# design.net
KiCad netlist of a schematic drawn in Altium Designer
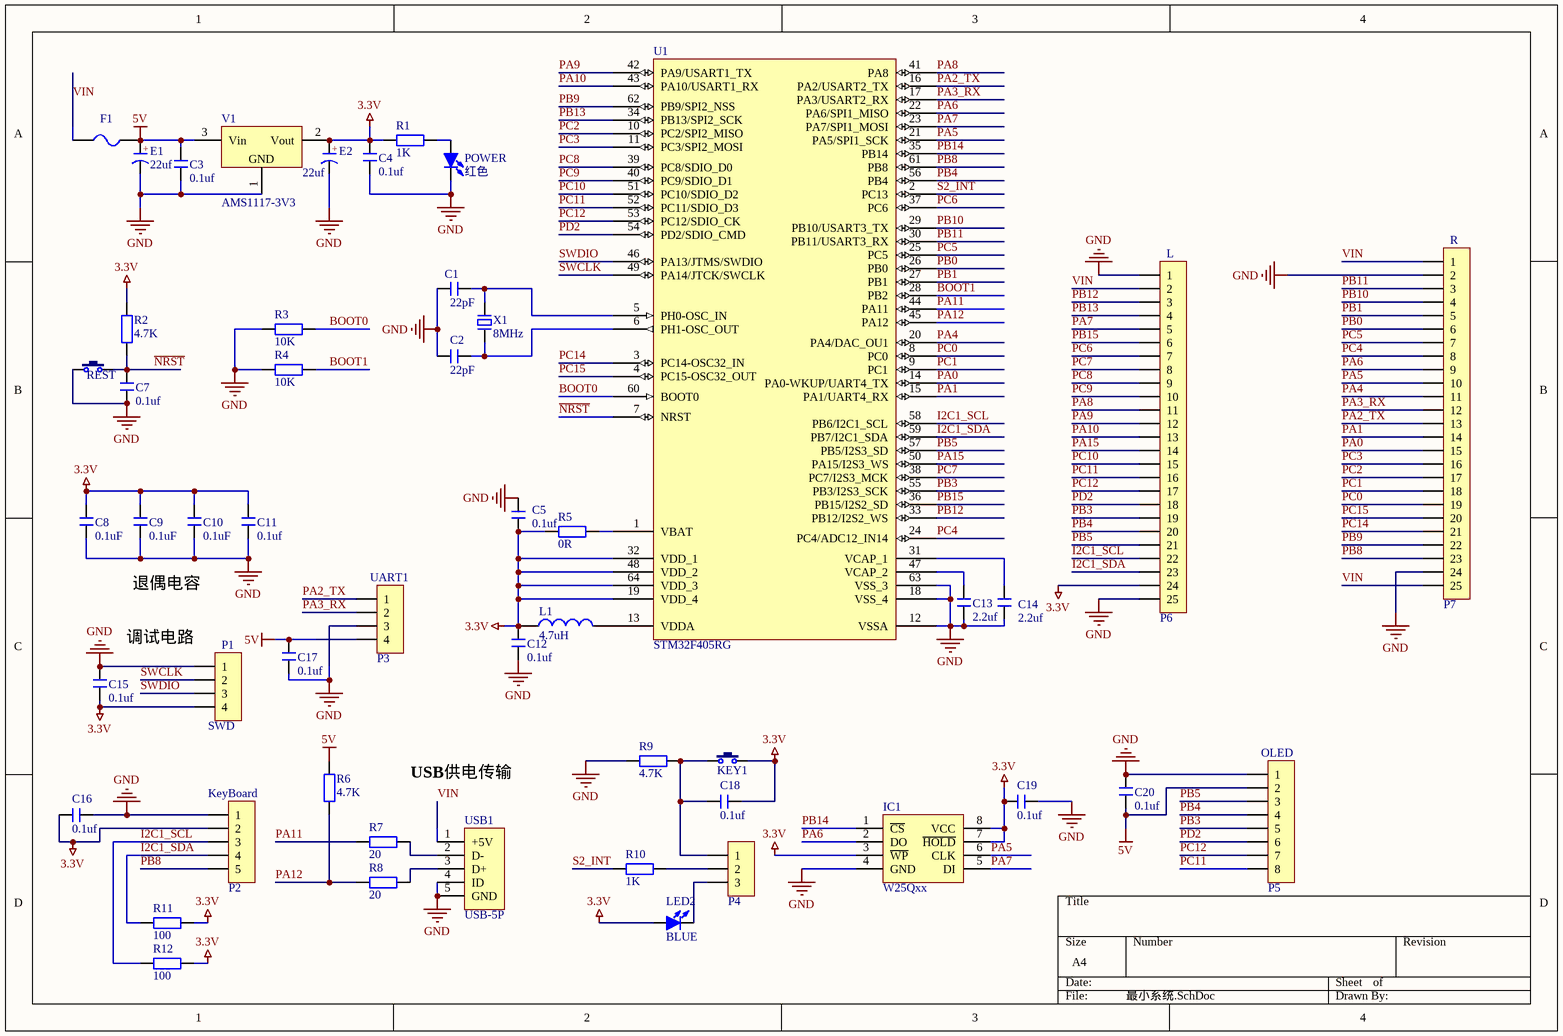
[diagram p0: 最小系统.SchDoc]

(export (version "E")
  (design (tool "Eeschema 10.0.6"))
  (components
    (comp (ref "C1")
      (value "22pF")
      (footprint "C 0603_M")
      (description "无极性贴片电容")
      (fields (field (name "版权归属") "源创客"))
      (libsource (lib "3.1   - 电阻-电容-电感") (part "C"))
    )
    (comp (ref "C2")
      (value "22pF")
      (footprint "C 0603_M")
      (description "无极性贴片电容")
      (fields (field (name "版权归属") "源创客"))
      (libsource (lib "3.1   - 电阻-电容-电感") (part "C"))
    )
    (comp (ref "C3")
      (value "0.1uf")
      (footprint "C 0603_M")
      (description "无极性贴片电容")
      (fields (field (name "版权归属") "源创客"))
      (libsource (lib "3.1   - 电阻-电容-电感") (part "C"))
    )
    (comp (ref "C4")
      (value "0.1uf")
      (footprint "C 0603_M")
      (description "无极性贴片电容")
      (fields (field (name "版权归属") "源创客"))
      (libsource (lib "3.1   - 电阻-电容-电感") (part "C"))
    )
    (comp (ref "C5")
      (value "0.1uf")
      (footprint "C 0603_M")
      (description "无极性贴片电容")
      (fields (field (name "版权归属") "源创客"))
      (libsource (lib "3.1   - 电阻-电容-电感") (part "C"))
    )
    (comp (ref "C7")
      (value "0.1uf")
      (footprint "C 0603_M")
      (description "无极性贴片电容")
      (fields (field (name "版权归属") "源创客"))
      (libsource (lib "3.1   - 电阻-电容-电感") (part "C"))
    )
    (comp (ref "C8")
      (value "0.1uF")
      (footprint "C 0603_M")
      (description "无极性贴片电容")
      (fields (field (name "版权归属") "源创客"))
      (libsource (lib "3.1   - 电阻-电容-电感") (part "C"))
    )
    (comp (ref "C9")
      (value "0.1uF")
      (footprint "C 0603_M")
      (description "无极性贴片电容")
      (fields (field (name "版权归属") "源创客"))
      (libsource (lib "3.1   - 电阻-电容-电感") (part "C"))
    )
    (comp (ref "C10")
      (value "0.1uF")
      (footprint "C 0603_M")
      (description "无极性贴片电容")
      (fields (field (name "版权归属") "源创客"))
      (libsource (lib "3.1   - 电阻-电容-电感") (part "C"))
    )
    (comp (ref "C11")
      (value "0.1uf")
      (footprint "C 0603_M")
      (description "无极性贴片电容")
      (fields (field (name "版权归属") "源创客"))
      (libsource (lib "3.1   - 电阻-电容-电感") (part "C"))
    )
    (comp (ref "C12")
      (value "0.1uf")
      (footprint "C 0603_M")
      (description "无极性贴片电容")
      (fields (field (name "版权归属") "源创客"))
      (libsource (lib "3.1   - 电阻-电容-电感") (part "C"))
    )
    (comp (ref "C13")
      (value "2.2uf")
      (footprint "C 0603_M")
      (description "无极性贴片电容")
      (fields (field (name "版权归属") "源创客"))
      (libsource (lib "3.1   - 电阻-电容-电感") (part "C"))
    )
    (comp (ref "C14")
      (value "2.2uf")
      (footprint "C 0603_M")
      (description "无极性贴片电容")
      (fields (field (name "版权归属") "源创客"))
      (libsource (lib "3.1   - 电阻-电容-电感") (part "C"))
    )
    (comp (ref "C15")
      (value "0.1uf")
      (footprint "C 0603_M")
      (description "无极性贴片电容")
      (fields (field (name "版权归属") "源创客"))
      (libsource (lib "3.1   - 电阻-电容-电感") (part "C"))
    )
    (comp (ref "C16")
      (value "0.1uf")
      (footprint "C 0603_M")
      (description "无极性贴片电容")
      (fields (field (name "版权归属") "源创客"))
      (libsource (lib "3.1   - 电阻-电容-电感") (part "C"))
    )
    (comp (ref "C17")
      (value "0.1uf")
      (footprint "C 0603_M")
      (description "无极性贴片电容")
      (fields (field (name "版权归属") "源创客"))
      (libsource (lib "3.1   - 电阻-电容-电感") (part "C"))
    )
    (comp (ref "C18")
      (value "0.1uf")
      (footprint "C 0603_M")
      (description "无极性贴片电容")
      (fields (field (name "版权归属") "源创客"))
      (libsource (lib "3.1   - 电阻-电容-电感") (part "C"))
    )
    (comp (ref "C19")
      (value "0.1uf")
      (footprint "C 0603_M")
      (description "无极性贴片电容")
      (fields (field (name "版权归属") "源创客"))
      (libsource (lib "3.1   - 电阻-电容-电感") (part "C"))
    )
    (comp (ref "C20")
      (value "0.1uf")
      (footprint "C 0603_M")
      (description "无极性贴片电容")
      (fields (field (name "版权归属") "源创客"))
      (libsource (lib "3.1   - 电阻-电容-电感") (part "C"))
    )
    (comp (ref "E1")
      (value "22uf")
      (footprint "CD B(3528)")
      (description "贴片钽电容")
      (fields (field (name "版权归属") "源创客"))
      (libsource (lib "3.1   - 电阻-电容-电感") (part "C-CD"))
    )
    (comp (ref "E2")
      (value "22uf")
      (footprint "CD B(3528)")
      (description "贴片钽电容")
      (fields (field (name "版权归属") "源创客"))
      (libsource (lib "3.1   - 电阻-电容-电感") (part "C-CD"))
    )
    (comp (ref "F1")
      (value "~")
      (footprint "FU 0603")
      (description "贴片保险丝")
      (fields (field (name "版权归属") "源创客"))
      (libsource (lib "10.1 - 保险丝-晶振") (part "FU"))
    )
    (comp (ref "IC1")
      (value "W25Qxx")
      (footprint "SOP8W_L")
      (description "外置Flash")
      (fields (field (name "版权归属") "源创客"))
      (libsource (lib "1.1   - IC芯片") (part "W25Qxx"))
    )
    (comp (ref "KEY1")
      (value "3x6x5")
      (footprint "TSW SMD-3*6*5")
      (description "3x6轻触开关")
      (fields (field (name "版权归属") "源创客"))
      (libsource (lib "5.1   - 按键-开关") (part "TSW 3x6"))
    )
    (comp (ref "L1")
      (value "4.7uH")
      (footprint "L 0603")
      (description "小功率贴片电感")
      (fields (field (name "版权归属") "源创客"))
      (libsource (lib "3.1   - 电阻-电容-电感") (part "L"))
    )
    (comp (ref "LED2")
      (value "BLUE")
      (footprint "LED 0603B")
      (description "贴片LED")
      (fields (field (name "版权归属") "源创客"))
      (libsource (lib "9.1   - LED") (part "LED-SMD"))
    )
    (comp (ref "P1")
      (value "HDR-1X4")
      (footprint "HDR2.54-LI-4P")
      (description "4P接插件")
      (fields (field (name "版权归属") "源创客"))
      (libsource (lib "4.5   - 接插件-脚距2.54") (part "Header 4"))
    )
    (comp (ref "P2")
      (value "HDR-1X5")
      (footprint "HDR2.54-LI-5P")
      (description "5P接插件")
      (fields (field (name "版权归属") "源创客"))
      (libsource (lib "4.5   - 接插件-脚距2.54") (part "Header 5"))
    )
    (comp (ref "P3")
      (value "HDR-1X4")
      (footprint "HDR2.54-LI-4P")
      (description "4P接插件")
      (fields (field (name "版权归属") "源创客"))
      (libsource (lib "4.5   - 接插件-脚距2.54") (part "Header 4"))
    )
    (comp (ref "P4")
      (value "HDR-1X3")
      (footprint "HDR2.54-LI-3P")
      (description "3P接插件")
      (fields (field (name "版权归属") "源创客"))
      (libsource (lib "4.5   - 接插件-脚距2.54") (part "Header 3"))
    )
    (comp (ref "P5")
      (value "HDR-1X8")
      (footprint "HDR2.54-LI-8P")
      (description "8P接插件")
      (fields (field (name "版权归属") "源创客"))
      (libsource (lib "4.5   - 接插件-脚距2.54") (part "Header 8"))
    )
    (comp (ref "P6")
      (value "FPC1.0-25P")
      (footprint "HDR2.54-L1-25P")
      (description "FPC连接器")
      (fields (field (name "版权归属") "源创客"))
      (libsource (lib "4.14 - FPC连接器") (part "FPC-25P"))
    )
    (comp (ref "P7")
      (value "FPC1.0-25P")
      (footprint "HDR2.54-L1-25P")
      (description "FPC连接器")
      (fields (field (name "版权归属") "源创客"))
      (libsource (lib "4.14 - FPC连接器") (part "FPC-25P"))
    )
    (comp (ref "POWER")
      (value "红色")
      (footprint "LED 0603W")
      (description "贴片LED")
      (fields (field (name "版权归属") "源创客"))
      (libsource (lib "9.1   - LED") (part "LED-SMD"))
    )
    (comp (ref "R1")
      (value "1K")
      (footprint "R 0603_M")
      (description "贴片电阻")
      (fields (field (name "版权归属") "源创客"))
      (libsource (lib "3.1   - 电阻-电容-电感") (part "R"))
    )
    (comp (ref "R2")
      (value "4.7K")
      (footprint "R 0603_M")
      (description "贴片电阻")
      (fields (field (name "版权归属") "源创客"))
      (libsource (lib "3.1   - 电阻-电容-电感") (part "R"))
    )
    (comp (ref "R3")
      (value "10K")
      (footprint "R 0603_M")
      (description "贴片电阻")
      (fields (field (name "版权归属") "源创客"))
      (libsource (lib "3.1   - 电阻-电容-电感") (part "R"))
    )
    (comp (ref "R4")
      (value "10K")
      (footprint "R 0603_M")
      (description "贴片电阻")
      (fields (field (name "版权归属") "源创客"))
      (libsource (lib "3.1   - 电阻-电容-电感") (part "R"))
    )
    (comp (ref "R5")
      (value "0R")
      (footprint "R 0603_M")
      (description "贴片电阻")
      (fields (field (name "版权归属") "源创客"))
      (libsource (lib "3.1   - 电阻-电容-电感") (part "R"))
    )
    (comp (ref "R6")
      (value "4.7K")
      (footprint "R 0603_M")
      (description "贴片电阻")
      (fields (field (name "版权归属") "源创客"))
      (libsource (lib "3.1   - 电阻-电容-电感") (part "R"))
    )
    (comp (ref "R7")
      (value "20")
      (footprint "R 0603_M")
      (description "贴片电阻")
      (fields (field (name "版权归属") "源创客"))
      (libsource (lib "3.1   - 电阻-电容-电感") (part "R"))
    )
    (comp (ref "R8")
      (value "20")
      (footprint "R 0603_M")
      (description "贴片电阻")
      (fields (field (name "版权归属") "源创客"))
      (libsource (lib "3.1   - 电阻-电容-电感") (part "R"))
    )
    (comp (ref "R9")
      (value "4.7K")
      (footprint "R 0603_M")
      (description "贴片电阻")
      (fields (field (name "版权归属") "源创客"))
      (libsource (lib "3.1   - 电阻-电容-电感") (part "R"))
    )
    (comp (ref "R10")
      (value "1K")
      (footprint "R 0603_M")
      (description "贴片电阻")
      (fields (field (name "版权归属") "源创客"))
      (libsource (lib "3.1   - 电阻-电容-电感") (part "R"))
    )
    (comp (ref "R11")
      (value "100")
      (footprint "R 0603_M")
      (description "贴片电阻")
      (fields (field (name "版权归属") "源创客"))
      (libsource (lib "3.1   - 电阻-电容-电感") (part "R"))
    )
    (comp (ref "R12")
      (value "100")
      (footprint "R 0603_M")
      (description "贴片电阻")
      (fields (field (name "版权归属") "源创客"))
      (libsource (lib "3.1   - 电阻-电容-电感") (part "R"))
    )
    (comp (ref "REST")
      (value "3x6x5")
      (footprint "TSW SMD-3*6*5")
      (description "3x6轻触开关")
      (fields (field (name "版权归属") "源创客"))
      (libsource (lib "5.1   - 按键-开关") (part "TSW 3x6"))
    )
    (comp (ref "U1")
      (value "STM32F405RG")
      (footprint "LQFP64 10X10_N")
      (description "32位STM单片机")
      (fields (field (name "版权归属") "源创客"))
      (libsource (lib "2.1   - STM32系列单片机") (part "STM32F205RG"))
    )
    (comp (ref "USB1")
      (value "USB-5P")
      (footprint "USB-MICRO_E")
      (description "微型USB母座")
      (fields (field (name "版权归属") "源创客"))
      (libsource (lib "4.1   - 接口类") (part "USB-5P"))
    )
    (comp (ref "V1")
      (value "AMS1117-3V3")
      (footprint "SOT223_L")
      (description "三端稳压芯片")
      (fields (field (name "版权归属") "源创客"))
      (libsource (lib "1.3   - 电源类芯片") (part "AMS1117"))
    )
    (comp (ref "X1")
      (value "8MHz")
      (footprint "OSC 5032-2P")
      (description "2脚无源脚晶振")
      (fields (field (name "版权归属") "源创客"))
      (libsource (lib "10.1 - 保险丝-晶振") (part "XTAL-2P"))
    )
  )
  (nets
    (net (code "1") (name "/BOOT0") (class "Default")
      (node (ref "R3") (pin "2") (pinfunction "2_2") (pintype "passive"))
      (node (ref "U1") (pin "60") (pinfunction "BOOT0_60") (pintype "input"))
    )
    (net (code "2") (name "/BOOT1") (class "Default")
      (node (ref "R4") (pin "2") (pinfunction "2_2") (pintype "passive"))
      (node (ref "U1") (pin "28") (pinfunction "PB2_28") (pintype "bidirectional"))
    )
    (net (code "3") (name "/I2C1_SCL") (class "Default")
      (node (ref "P2") (pin "3") (pinfunction "3_3") (pintype "passive"))
      (node (ref "P6") (pin "22") (pinfunction "22_22") (pintype "passive"))
      (node (ref "R12") (pin "1") (pinfunction "1_1") (pintype "passive"))
      (node (ref "U1") (pin "58") (pinfunction "PB6/I2C1_SCL_58") (pintype "bidirectional"))
    )
    (net (code "4") (name "/I2C1_SDA") (class "Default")
      (node (ref "P2") (pin "4") (pinfunction "4_4") (pintype "passive"))
      (node (ref "P6") (pin "23") (pinfunction "23_23") (pintype "passive"))
      (node (ref "R11") (pin "1") (pinfunction "1_1") (pintype "passive"))
      (node (ref "U1") (pin "59") (pinfunction "PB7/I2C1_SDA_59") (pintype "bidirectional"))
    )
    (net (code "5") (name "/PA0") (class "Default")
      (node (ref "P7") (pin "15") (pinfunction "15_15") (pintype "passive"))
      (node (ref "U1") (pin "14") (pinfunction "PA0-WKUP/UART4_TX_14") (pintype "bidirectional"))
    )
    (net (code "6") (name "/PA1") (class "Default")
      (node (ref "P7") (pin "14") (pinfunction "14_14") (pintype "passive"))
      (node (ref "U1") (pin "15") (pinfunction "PA1/UART4_RX_15") (pintype "bidirectional"))
    )
    (net (code "7") (name "/PA2_TX") (class "Default")
      (node (ref "P3") (pin "1") (pinfunction "1_1") (pintype "passive"))
      (node (ref "P7") (pin "13") (pinfunction "13_13") (pintype "passive"))
      (node (ref "U1") (pin "16") (pinfunction "PA2/USART2_TX_16") (pintype "bidirectional"))
    )
    (net (code "8") (name "/PA3_RX") (class "Default")
      (node (ref "P3") (pin "2") (pinfunction "2_2") (pintype "passive"))
      (node (ref "P7") (pin "12") (pinfunction "12_12") (pintype "passive"))
      (node (ref "U1") (pin "17") (pinfunction "PA3/USART2_RX_17") (pintype "bidirectional"))
    )
    (net (code "9") (name "/PA4") (class "Default")
      (node (ref "P7") (pin "11") (pinfunction "11_11") (pintype "passive"))
      (node (ref "U1") (pin "20") (pinfunction "PA4/DAC_OU1_20") (pintype "bidirectional"))
    )
    (net (code "10") (name "/PA5") (class "Default")
      (node (ref "IC1") (pin "6") (pinfunction "CLK_6") (pintype "passive"))
      (node (ref "P7") (pin "10") (pinfunction "10_10") (pintype "passive"))
      (node (ref "U1") (pin "21") (pinfunction "PA5/SPI1_SCK_21") (pintype "bidirectional"))
    )
    (net (code "11") (name "/PA6") (class "Default")
      (node (ref "IC1") (pin "2") (pinfunction "DO_2") (pintype "passive"))
      (node (ref "P7") (pin "9") (pinfunction "9_9") (pintype "passive"))
      (node (ref "U1") (pin "22") (pinfunction "PA6/SPI1_MISO_22") (pintype "bidirectional"))
    )
    (net (code "12") (name "/PA7") (class "Default")
      (node (ref "IC1") (pin "5") (pinfunction "DI_5") (pintype "passive"))
      (node (ref "P6") (pin "5") (pinfunction "5_5") (pintype "passive"))
      (node (ref "U1") (pin "23") (pinfunction "PA7/SPI1_MOSI_23") (pintype "bidirectional"))
    )
    (net (code "13") (name "/PA8") (class "Default")
      (node (ref "P6") (pin "11") (pinfunction "11_11") (pintype "passive"))
      (node (ref "U1") (pin "41") (pinfunction "PA8_41") (pintype "bidirectional"))
    )
    (net (code "14") (name "/PA9") (class "Default")
      (node (ref "P6") (pin "12") (pinfunction "12_12") (pintype "passive"))
      (node (ref "U1") (pin "42") (pinfunction "PA9/USART1_TX_42") (pintype "bidirectional"))
    )
    (net (code "15") (name "/PA10") (class "Default")
      (node (ref "P6") (pin "13") (pinfunction "13_13") (pintype "passive"))
      (node (ref "U1") (pin "43") (pinfunction "PA10/USART1_RX_43") (pintype "bidirectional"))
    )
    (net (code "16") (name "/PA11") (class "Default")
      (node (ref "R7") (pin "1") (pinfunction "1_1") (pintype "passive"))
      (node (ref "U1") (pin "44") (pinfunction "PA11_44") (pintype "bidirectional"))
    )
    (net (code "17") (name "/PA12") (class "Default")
      (node (ref "R6") (pin "1") (pinfunction "1_1") (pintype "passive"))
      (node (ref "R8") (pin "1") (pinfunction "1_1") (pintype "passive"))
      (node (ref "U1") (pin "45") (pinfunction "PA12_45") (pintype "bidirectional"))
    )
    (net (code "18") (name "/PA15") (class "Default")
      (node (ref "P6") (pin "14") (pinfunction "14_14") (pintype "passive"))
      (node (ref "U1") (pin "50") (pinfunction "PA15/I2S3_WS_50") (pintype "bidirectional"))
    )
    (net (code "19") (name "/PB0") (class "Default")
      (node (ref "P7") (pin "6") (pinfunction "6_6") (pintype "passive"))
      (node (ref "U1") (pin "26") (pinfunction "PB0_26") (pintype "bidirectional"))
    )
    (net (code "20") (name "/PB1") (class "Default")
      (node (ref "P7") (pin "5") (pinfunction "5_5") (pintype "passive"))
      (node (ref "U1") (pin "27") (pinfunction "PB1_27") (pintype "bidirectional"))
    )
    (net (code "21") (name "/PB3") (class "Default")
      (node (ref "P5") (pin "5") (pinfunction "5_5") (pintype "passive"))
      (node (ref "P6") (pin "19") (pinfunction "19_19") (pintype "passive"))
      (node (ref "U1") (pin "55") (pinfunction "PB3/I2S3_SCK_55") (pintype "bidirectional"))
    )
    (net (code "22") (name "/PB4") (class "Default")
      (node (ref "P5") (pin "4") (pinfunction "4_4") (pintype "passive"))
      (node (ref "P6") (pin "20") (pinfunction "20_20") (pintype "passive"))
      (node (ref "U1") (pin "56") (pinfunction "PB4_56") (pintype "bidirectional"))
    )
    (net (code "23") (name "/PB5") (class "Default")
      (node (ref "P5") (pin "3") (pinfunction "3_3") (pintype "passive"))
      (node (ref "P6") (pin "21") (pinfunction "21_21") (pintype "passive"))
      (node (ref "U1") (pin "57") (pinfunction "PB5/I2S3_SD_57") (pintype "bidirectional"))
    )
    (net (code "24") (name "/PB8") (class "Default")
      (node (ref "P2") (pin "5") (pinfunction "5_5") (pintype "passive"))
      (node (ref "P7") (pin "23") (pinfunction "23_23") (pintype "passive"))
      (node (ref "U1") (pin "61") (pinfunction "PB8_61") (pintype "bidirectional"))
    )
    (net (code "25") (name "/PB9") (class "Default")
      (node (ref "P7") (pin "22") (pinfunction "22_22") (pintype "passive"))
      (node (ref "U1") (pin "62") (pinfunction "PB9/SPI2_NSS_62") (pintype "bidirectional"))
    )
    (net (code "26") (name "/PB10") (class "Default")
      (node (ref "P7") (pin "4") (pinfunction "4_4") (pintype "passive"))
      (node (ref "U1") (pin "29") (pinfunction "PB10/USART3_TX_29") (pintype "bidirectional"))
    )
    (net (code "27") (name "/PB11") (class "Default")
      (node (ref "P7") (pin "3") (pinfunction "3_3") (pintype "passive"))
      (node (ref "U1") (pin "30") (pinfunction "PB11/USART3_RX_30") (pintype "bidirectional"))
    )
    (net (code "28") (name "/PB12") (class "Default")
      (node (ref "P6") (pin "3") (pinfunction "3_3") (pintype "passive"))
      (node (ref "U1") (pin "33") (pinfunction "PB12/I2S2_WS_33") (pintype "bidirectional"))
    )
    (net (code "29") (name "/PB13") (class "Default")
      (node (ref "P6") (pin "4") (pinfunction "4_4") (pintype "passive"))
      (node (ref "U1") (pin "34") (pinfunction "PB13/SPI2_SCK_34") (pintype "bidirectional"))
    )
    (net (code "30") (name "/PB14") (class "Default")
      (node (ref "IC1") (pin "1") (pinfunction "~{CS}_1") (pintype "passive"))
      (node (ref "U1") (pin "35") (pinfunction "PB14_35") (pintype "bidirectional"))
    )
    (net (code "31") (name "/PB15") (class "Default")
      (node (ref "P6") (pin "6") (pinfunction "6_6") (pintype "passive"))
      (node (ref "U1") (pin "36") (pinfunction "PB15/I2S2_SD_36") (pintype "bidirectional"))
    )
    (net (code "32") (name "/PC0") (class "Default")
      (node (ref "P7") (pin "19") (pinfunction "19_19") (pintype "passive"))
      (node (ref "U1") (pin "8") (pinfunction "PC0_8") (pintype "bidirectional"))
    )
    (net (code "33") (name "/PC1") (class "Default")
      (node (ref "P7") (pin "18") (pinfunction "18_18") (pintype "passive"))
      (node (ref "U1") (pin "9") (pinfunction "PC1_9") (pintype "bidirectional"))
    )
    (net (code "34") (name "/PC2") (class "Default")
      (node (ref "P7") (pin "17") (pinfunction "17_17") (pintype "passive"))
      (node (ref "U1") (pin "10") (pinfunction "PC2/SPI2_MISO_10") (pintype "bidirectional"))
    )
    (net (code "35") (name "/PC3") (class "Default")
      (node (ref "P7") (pin "16") (pinfunction "16_16") (pintype "passive"))
      (node (ref "U1") (pin "11") (pinfunction "PC3/SPI2_MOSI_11") (pintype "bidirectional"))
    )
    (net (code "36") (name "/PC4") (class "Default")
      (node (ref "P7") (pin "8") (pinfunction "8_8") (pintype "passive"))
      (node (ref "U1") (pin "24") (pinfunction "PC4/ADC12_IN14_24") (pintype "bidirectional"))
    )
    (net (code "37") (name "/PC5") (class "Default")
      (node (ref "P7") (pin "7") (pinfunction "7_7") (pintype "passive"))
      (node (ref "U1") (pin "25") (pinfunction "PC5_25") (pintype "bidirectional"))
    )
    (net (code "38") (name "/PC6") (class "Default")
      (node (ref "P6") (pin "7") (pinfunction "7_7") (pintype "passive"))
      (node (ref "U1") (pin "37") (pinfunction "PC6_37") (pintype "bidirectional"))
    )
    (net (code "39") (name "/PC7") (class "Default")
      (node (ref "P6") (pin "8") (pinfunction "8_8") (pintype "passive"))
      (node (ref "U1") (pin "38") (pinfunction "PC7/I2S3_MCK_38") (pintype "bidirectional"))
    )
    (net (code "40") (name "/PC8") (class "Default")
      (node (ref "P6") (pin "9") (pinfunction "9_9") (pintype "passive"))
      (node (ref "U1") (pin "39") (pinfunction "PC8/SDIO_D0_39") (pintype "bidirectional"))
    )
    (net (code "41") (name "/PC9") (class "Default")
      (node (ref "P6") (pin "10") (pinfunction "10_10") (pintype "passive"))
      (node (ref "U1") (pin "40") (pinfunction "PC9/SDIO_D1_40") (pintype "bidirectional"))
    )
    (net (code "42") (name "/PC10") (class "Default")
      (node (ref "P6") (pin "15") (pinfunction "15_15") (pintype "passive"))
      (node (ref "U1") (pin "51") (pinfunction "PC10/SDIO_D2_51") (pintype "bidirectional"))
    )
    (net (code "43") (name "/PC11") (class "Default")
      (node (ref "P5") (pin "8") (pinfunction "8_8") (pintype "passive"))
      (node (ref "P6") (pin "16") (pinfunction "16_16") (pintype "passive"))
      (node (ref "U1") (pin "52") (pinfunction "PC11/SDIO_D3_52") (pintype "bidirectional"))
    )
    (net (code "44") (name "/PC12") (class "Default")
      (node (ref "P5") (pin "7") (pinfunction "7_7") (pintype "passive"))
      (node (ref "P6") (pin "17") (pinfunction "17_17") (pintype "passive"))
      (node (ref "U1") (pin "53") (pinfunction "PC12/SDIO_CK_53") (pintype "bidirectional"))
    )
    (net (code "45") (name "/PC14") (class "Default")
      (node (ref "P7") (pin "21") (pinfunction "21_21") (pintype "passive"))
      (node (ref "U1") (pin "3") (pinfunction "PC14-OSC32_IN_3") (pintype "bidirectional"))
    )
    (net (code "46") (name "/PC15") (class "Default")
      (node (ref "P7") (pin "20") (pinfunction "20_20") (pintype "passive"))
      (node (ref "U1") (pin "4") (pinfunction "PC15-OSC32_OUT_4") (pintype "bidirectional"))
    )
    (net (code "47") (name "/PD2") (class "Default")
      (node (ref "P5") (pin "6") (pinfunction "6_6") (pintype "passive"))
      (node (ref "P6") (pin "18") (pinfunction "18_18") (pintype "passive"))
      (node (ref "U1") (pin "54") (pinfunction "PD2/SDIO_CMD_54") (pintype "bidirectional"))
    )
    (net (code "48") (name "/S2_INT") (class "Default")
      (node (ref "R10") (pin "2") (pinfunction "2_2") (pintype "passive"))
      (node (ref "U1") (pin "2") (pinfunction "PC13_2") (pintype "bidirectional"))
    )
    (net (code "49") (name "/SWCLK") (class "Default")
      (node (ref "P1") (pin "2") (pinfunction "2_2") (pintype "passive"))
      (node (ref "U1") (pin "49") (pinfunction "PA14/JTCK/SWCLK_49") (pintype "bidirectional"))
    )
    (net (code "50") (name "/SWDIO") (class "Default")
      (node (ref "P1") (pin "3") (pinfunction "3_3") (pintype "passive"))
      (node (ref "U1") (pin "46") (pinfunction "PA13/JTMS/SWDIO_46") (pintype "bidirectional"))
    )
    (net (code "51") (name "/VIN") (class "Default")
      (node (ref "F1") (pin "1") (pinfunction "1_1") (pintype "passive"))
      (node (ref "P6") (pin "2") (pinfunction "2_2") (pintype "passive"))
      (node (ref "P7") (pin "1") (pinfunction "1_1") (pintype "passive"))
      (node (ref "P7") (pin "25") (pinfunction "25_25") (pintype "passive"))
      (node (ref "USB1") (pin "1") (pinfunction "+5V_1") (pintype "passive"))
    )
    (net (code "52") (name "/~{NRST}") (class "Default")
      (node (ref "C7") (pin "2") (pinfunction "2_2") (pintype "passive"))
      (node (ref "R2") (pin "1") (pinfunction "1_1") (pintype "passive"))
      (node (ref "REST") (pin "2") (pinfunction "2_2") (pintype "passive"))
      (node (ref "U1") (pin "7") (pinfunction "NRST_7") (pintype "bidirectional"))
    )
    (net (code "53") (name "3.3V") (class "Default")
      (node (ref "C10") (pin "2") (pinfunction "2_2") (pintype "passive"))
      (node (ref "C11") (pin "2") (pinfunction "2_2") (pintype "passive"))
      (node (ref "C12") (pin "2") (pinfunction "2_2") (pintype "passive"))
      (node (ref "C15") (pin "1") (pinfunction "1_1") (pintype "passive"))
      (node (ref "C16") (pin "1") (pinfunction "1_1") (pintype "passive"))
      (node (ref "C18") (pin "2") (pinfunction "2_2") (pintype "passive"))
      (node (ref "C19") (pin "1") (pinfunction "1_1") (pintype "passive"))
      (node (ref "C4") (pin "2") (pinfunction "2_2") (pintype "passive"))
      (node (ref "C5") (pin "1") (pinfunction "1_1") (pintype "passive"))
      (node (ref "C8") (pin "2") (pinfunction "2_2") (pintype "passive"))
      (node (ref "C9") (pin "2") (pinfunction "2_2") (pintype "passive"))
      (node (ref "E2") (pin "1") (pinfunction "A_1") (pintype "passive"))
      (node (ref "IC1") (pin "3") (pinfunction "~{WP}_3") (pintype "passive"))
      (node (ref "IC1") (pin "7") (pinfunction "~{HOLD}_7") (pintype "passive"))
      (node (ref "IC1") (pin "8") (pinfunction "VCC_8") (pintype "passive"))
      (node (ref "KEY1") (pin "2") (pinfunction "2_2") (pintype "passive"))
      (node (ref "L1") (pin "1") (pinfunction "1_1") (pintype "passive"))
      (node (ref "LED2") (pin "1") (pinfunction "A_1") (pintype "passive"))
      (node (ref "P1") (pin "4") (pinfunction "4_4") (pintype "passive"))
      (node (ref "P2") (pin "2") (pinfunction "2_2") (pintype "passive"))
      (node (ref "P6") (pin "24") (pinfunction "24_24") (pintype "passive"))
      (node (ref "R1") (pin "1") (pinfunction "1_1") (pintype "passive"))
      (node (ref "R11") (pin "2") (pinfunction "2_2") (pintype "passive"))
      (node (ref "R12") (pin "2") (pinfunction "2_2") (pintype "passive"))
      (node (ref "R2") (pin "2") (pinfunction "2_2") (pintype "passive"))
      (node (ref "R5") (pin "1") (pinfunction "1_1") (pintype "passive"))
      (node (ref "U1") (pin "19") (pinfunction "VDD_4_19") (pintype "power_in"))
      (node (ref "U1") (pin "32") (pinfunction "VDD_1_32") (pintype "power_in"))
      (node (ref "U1") (pin "48") (pinfunction "VDD_2_48") (pintype "power_in"))
      (node (ref "U1") (pin "64") (pinfunction "VDD_3_64") (pintype "power_in"))
      (node (ref "V1") (pin "2") (pinfunction "Vout_2") (pintype "passive"))
    )
    (net (code "54") (name "5V") (class "Default")
      (node (ref "C17") (pin "2") (pinfunction "2_2") (pintype "passive"))
      (node (ref "C20") (pin "1") (pinfunction "1_1") (pintype "passive"))
      (node (ref "C3") (pin "2") (pinfunction "2_2") (pintype "passive"))
      (node (ref "E1") (pin "1") (pinfunction "A_1") (pintype "passive"))
      (node (ref "F1") (pin "2") (pinfunction "2_2") (pintype "passive"))
      (node (ref "P3") (pin "4") (pinfunction "4_4") (pintype "passive"))
      (node (ref "P5") (pin "2") (pinfunction "2_2") (pintype "passive"))
      (node (ref "R6") (pin "2") (pinfunction "2_2") (pintype "passive"))
      (node (ref "V1") (pin "3") (pinfunction "Vin_3") (pintype "passive"))
    )
    (net (code "55") (name "GND") (class "Default")
      (node (ref "C1") (pin "1") (pinfunction "1_1") (pintype "passive"))
      (node (ref "C10") (pin "1") (pinfunction "1_1") (pintype "passive"))
      (node (ref "C11") (pin "1") (pinfunction "1_1") (pintype "passive"))
      (node (ref "C12") (pin "1") (pinfunction "1_1") (pintype "passive"))
      (node (ref "C13") (pin "1") (pinfunction "1_1") (pintype "passive"))
      (node (ref "C14") (pin "1") (pinfunction "1_1") (pintype "passive"))
      (node (ref "C15") (pin "2") (pinfunction "2_2") (pintype "passive"))
      (node (ref "C16") (pin "2") (pinfunction "2_2") (pintype "passive"))
      (node (ref "C17") (pin "1") (pinfunction "1_1") (pintype "passive"))
      (node (ref "C19") (pin "2") (pinfunction "2_2") (pintype "passive"))
      (node (ref "C2") (pin "1") (pinfunction "1_1") (pintype "passive"))
      (node (ref "C20") (pin "2") (pinfunction "2_2") (pintype "passive"))
      (node (ref "C3") (pin "1") (pinfunction "1_1") (pintype "passive"))
      (node (ref "C4") (pin "1") (pinfunction "1_1") (pintype "passive"))
      (node (ref "C5") (pin "2") (pinfunction "2_2") (pintype "passive"))
      (node (ref "C7") (pin "1") (pinfunction "1_1") (pintype "passive"))
      (node (ref "C8") (pin "1") (pinfunction "1_1") (pintype "passive"))
      (node (ref "C9") (pin "1") (pinfunction "1_1") (pintype "passive"))
      (node (ref "E1") (pin "2") (pinfunction "K_2") (pintype "passive"))
      (node (ref "E2") (pin "2") (pinfunction "K_2") (pintype "passive"))
      (node (ref "IC1") (pin "4") (pinfunction "GND_4") (pintype "passive"))
      (node (ref "P1") (pin "1") (pinfunction "1_1") (pintype "passive"))
      (node (ref "P2") (pin "1") (pinfunction "1_1") (pintype "passive"))
      (node (ref "P3") (pin "3") (pinfunction "3_3") (pintype "passive"))
      (node (ref "P5") (pin "1") (pinfunction "1_1") (pintype "passive"))
      (node (ref "P6") (pin "1") (pinfunction "1_1") (pintype "passive"))
      (node (ref "P6") (pin "25") (pinfunction "25_25") (pintype "passive"))
      (node (ref "P7") (pin "2") (pinfunction "2_2") (pintype "passive"))
      (node (ref "P7") (pin "24") (pinfunction "24_24") (pintype "passive"))
      (node (ref "POWER") (pin "2") (pinfunction "K_2") (pintype "passive"))
      (node (ref "R3") (pin "1") (pinfunction "1_1") (pintype "passive"))
      (node (ref "R4") (pin "1") (pinfunction "1_1") (pintype "passive"))
      (node (ref "R9") (pin "1") (pinfunction "1_1") (pintype "passive"))
      (node (ref "REST") (pin "1") (pinfunction "1_1") (pintype "passive"))
      (node (ref "U1") (pin "12") (pinfunction "VSSA_12") (pintype "power_in"))
      (node (ref "U1") (pin "18") (pinfunction "VSS_4_18") (pintype "power_in"))
      (node (ref "U1") (pin "63") (pinfunction "VSS_3_63") (pintype "power_in"))
      (node (ref "USB1") (pin "4") (pinfunction "ID_4") (pintype "passive"))
      (node (ref "USB1") (pin "5") (pinfunction "GND_5") (pintype "passive"))
      (node (ref "V1") (pin "1") (pinfunction "GND_1") (pintype "passive"))
    )
    (net (code "56") (name "Net-(C18-Pad1)") (class "Default")
      (node (ref "C18") (pin "1") (pinfunction "1_1") (pintype "passive"))
      (node (ref "KEY1") (pin "1") (pinfunction "1_1") (pintype "passive"))
      (node (ref "P4") (pin "1") (pinfunction "1_1") (pintype "passive"))
      (node (ref "R9") (pin "2") (pinfunction "2_2") (pintype "passive"))
    )
    (net (code "57") (name "Net-(LED2-K)") (class "Default")
      (node (ref "LED2") (pin "2") (pinfunction "K_2") (pintype "passive"))
      (node (ref "P4") (pin "3") (pinfunction "3_3") (pintype "passive"))
    )
    (net (code "58") (name "Net-(P4-Pad2)") (class "Default")
      (node (ref "P4") (pin "2") (pinfunction "2_2") (pintype "passive"))
      (node (ref "R10") (pin "1") (pinfunction "1_1") (pintype "passive"))
    )
    (net (code "59") (name "Net-(POWER-A)") (class "Default")
      (node (ref "POWER") (pin "1") (pinfunction "A_1") (pintype "passive"))
      (node (ref "R1") (pin "2") (pinfunction "2_2") (pintype "passive"))
    )
    (net (code "60") (name "Net-(U1-PH0-OSC_IN)") (class "Default")
      (node (ref "C1") (pin "2") (pinfunction "2_2") (pintype "passive"))
      (node (ref "U1") (pin "5") (pinfunction "PH0-OSC_IN_5") (pintype "input"))
      (node (ref "X1") (pin "2") (pinfunction "2_2") (pintype "passive"))
    )
    (net (code "61") (name "Net-(U1-PH1-OSC_OUT)") (class "Default")
      (node (ref "C2") (pin "2") (pinfunction "2_2") (pintype "passive"))
      (node (ref "U1") (pin "6") (pinfunction "PH1-OSC_OUT_6") (pintype "output"))
      (node (ref "X1") (pin "1") (pinfunction "1_1") (pintype "passive"))
    )
    (net (code "62") (name "Net-(U1-VBAT)") (class "Default")
      (node (ref "R5") (pin "2") (pinfunction "2_2") (pintype "passive"))
      (node (ref "U1") (pin "1") (pinfunction "VBAT_1") (pintype "power_in"))
    )
    (net (code "63") (name "Net-(U1-VCAP_1)") (class "Default")
      (node (ref "C14") (pin "2") (pinfunction "2_2") (pintype "passive"))
      (node (ref "U1") (pin "31") (pinfunction "VCAP_1_31") (pintype "passive"))
    )
    (net (code "64") (name "Net-(U1-VCAP_2)") (class "Default")
      (node (ref "C13") (pin "2") (pinfunction "2_2") (pintype "passive"))
      (node (ref "U1") (pin "47") (pinfunction "VCAP_2_47") (pintype "passive"))
    )
    (net (code "65") (name "Net-(U1-VDDA)") (class "Default")
      (node (ref "L1") (pin "2") (pinfunction "2_2") (pintype "passive"))
      (node (ref "U1") (pin "13") (pinfunction "VDDA_13") (pintype "power_in"))
    )
    (net (code "66") (name "Net-(USB1-D+)") (class "Default")
      (node (ref "R8") (pin "2") (pinfunction "2_2") (pintype "passive"))
      (node (ref "USB1") (pin "3") (pinfunction "D+_3") (pintype "passive"))
    )
    (net (code "67") (name "Net-(USB1-D-)") (class "Default")
      (node (ref "R7") (pin "2") (pinfunction "2_2") (pintype "passive"))
      (node (ref "USB1") (pin "2") (pinfunction "D-_2") (pintype "passive"))
    )
  )
)
